# sinktheship.net
KiCad netlist of a schematic drawn in EAGLE
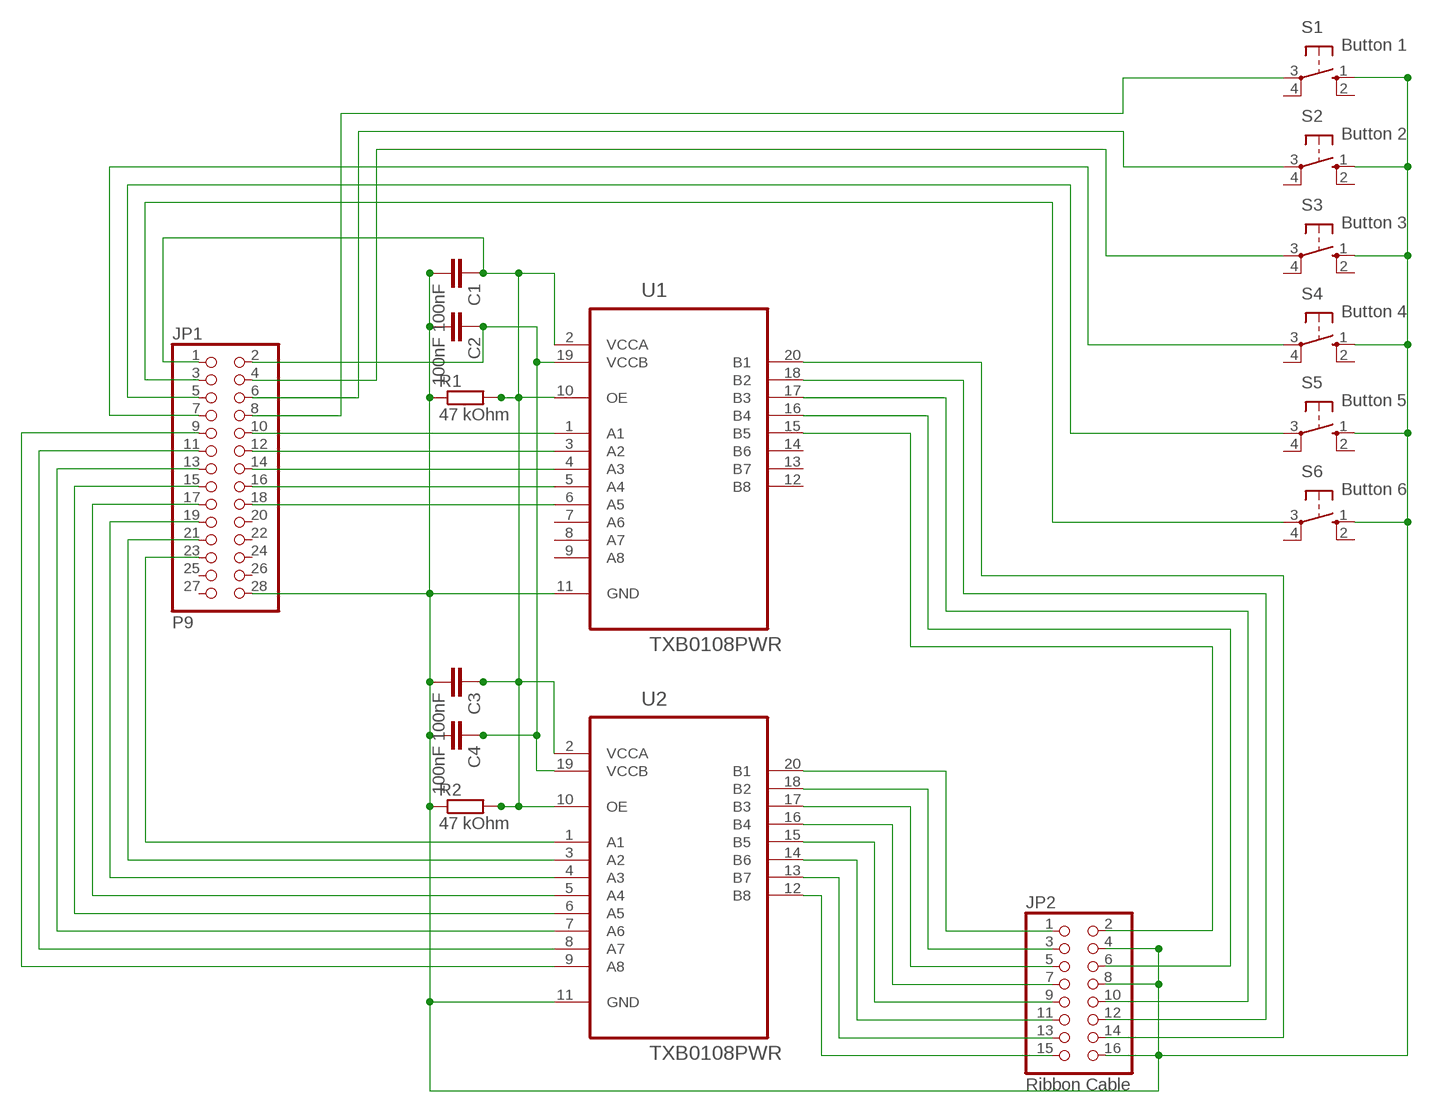
[diagram p0: schematic, sheet 1]

(export (version "E")
  (design (tool "Eeschema 10.0.6"))
  (components
    (comp (ref "C1")
      (value "100nF")
      (footprint "eagle-import:C0603")
      (libsource (lib "eagle-import") (part "C-EUC0603"))
    )
    (comp (ref "C2")
      (value "100nF")
      (footprint "eagle-import:C0603")
      (libsource (lib "eagle-import") (part "C-EUC0603"))
    )
    (comp (ref "C3")
      (value "100nF")
      (footprint "eagle-import:C0603")
      (libsource (lib "eagle-import") (part "C-EUC0603"))
    )
    (comp (ref "C4")
      (value "100nF")
      (footprint "eagle-import:C0603")
      (libsource (lib "eagle-import") (part "C-EUC0603"))
    )
    (comp (ref "JP1")
      (value "P9")
      (footprint "eagle-import:2X14")
      (libsource (lib "eagle-import") (part "PINHD-2X14"))
    )
    (comp (ref "JP2")
      (value "Ribbon Cable")
      (footprint "eagle-import:2X08")
      (libsource (lib "eagle-import") (part "PINHD-2X8"))
    )
    (comp (ref "R1")
      (value "47 kOhm")
      (footprint "eagle-import:R0603")
      (libsource (lib "eagle-import") (part "R-EU_R0603"))
    )
    (comp (ref "R2")
      (value "47 kOhm")
      (footprint "eagle-import:R0603")
      (libsource (lib "eagle-import") (part "R-EU_R0603"))
    )
    (comp (ref "S1")
      (value "Button 1")
      (footprint "eagle-import:B3F-10XX")
      (fields (field (name "MPN") "B3F-1000"))
      (libsource (lib "eagle-import") (part "10-XX"))
    )
    (comp (ref "S2")
      (value "Button 2")
      (footprint "eagle-import:B3F-10XX")
      (fields (field (name "MPN") "B3F-1000"))
      (libsource (lib "eagle-import") (part "10-XX"))
    )
    (comp (ref "S3")
      (value "Button 3")
      (footprint "eagle-import:B3F-10XX")
      (fields (field (name "MPN") "B3F-1000"))
      (libsource (lib "eagle-import") (part "10-XX"))
    )
    (comp (ref "S4")
      (value "Button 4")
      (footprint "eagle-import:B3F-10XX")
      (fields (field (name "MPN") "B3F-1000"))
      (libsource (lib "eagle-import") (part "10-XX"))
    )
    (comp (ref "S5")
      (value "Button 5")
      (footprint "eagle-import:B3F-10XX")
      (fields (field (name "MPN") "B3F-1000"))
      (libsource (lib "eagle-import") (part "10-XX"))
    )
    (comp (ref "S6")
      (value "Button 6")
      (footprint "eagle-import:B3F-10XX")
      (fields (field (name "MPN") "B3F-1000"))
      (libsource (lib "eagle-import") (part "10-XX"))
    )
    (comp (ref "U1")
      (value "TXB0108PWR")
      (footprint "eagle-import:SOP65P640X120-20N")
      (libsource (lib "eagle-import") (part "TXB0108PWR"))
    )
    (comp (ref "U2")
      (value "TXB0108PWR")
      (footprint "eagle-import:SOP65P640X120-20N")
      (libsource (lib "eagle-import") (part "TXB0108PWR"))
    )
  )
  (nets
    (net (code "1") (name "Net-(S1-P)") (class "Default")
      (node (ref "JP1") (pin "8") (pinfunction "8_8") (pintype "passive"))
      (node (ref "S1") (pin "3") (pinfunction "P_3") (pintype "passive"))
    )
    (net (code "2") (name "Net-(S1-S)") (class "Default")
      (node (ref "C1") (pin "2") (pinfunction "2_2") (pintype "passive"))
      (node (ref "C2") (pin "2") (pinfunction "2_2") (pintype "passive"))
      (node (ref "C3") (pin "2") (pinfunction "2_2") (pintype "passive"))
      (node (ref "C4") (pin "2") (pinfunction "2_2") (pintype "passive"))
      (node (ref "JP1") (pin "28") (pinfunction "28_28") (pintype "passive"))
      (node (ref "JP2") (pin "16") (pinfunction "16_16") (pintype "passive"))
      (node (ref "JP2") (pin "4") (pinfunction "4_4") (pintype "passive"))
      (node (ref "JP2") (pin "8") (pinfunction "8_8") (pintype "passive"))
      (node (ref "R1") (pin "1") (pinfunction "1_1") (pintype "passive"))
      (node (ref "R2") (pin "1") (pinfunction "1_1") (pintype "passive"))
      (node (ref "S1") (pin "1") (pinfunction "S_1") (pintype "passive"))
      (node (ref "S2") (pin "1") (pinfunction "S_1") (pintype "passive"))
      (node (ref "S3") (pin "1") (pinfunction "S_1") (pintype "passive"))
      (node (ref "S4") (pin "1") (pinfunction "S_1") (pintype "passive"))
      (node (ref "S5") (pin "1") (pinfunction "S_1") (pintype "passive"))
      (node (ref "S6") (pin "1") (pinfunction "S_1") (pintype "passive"))
      (node (ref "U1") (pin "11") (pinfunction "GND_11") (pintype "passive"))
      (node (ref "U2") (pin "11") (pinfunction "GND_11") (pintype "passive"))
    )
    (net (code "3") (name "Net-(S2-P)") (class "Default")
      (node (ref "JP1") (pin "6") (pinfunction "6_6") (pintype "passive"))
      (node (ref "S2") (pin "3") (pinfunction "P_3") (pintype "passive"))
    )
    (net (code "4") (name "Net-(S3-P)") (class "Default")
      (node (ref "JP1") (pin "4") (pinfunction "4_4") (pintype "passive"))
      (node (ref "S3") (pin "3") (pinfunction "P_3") (pintype "passive"))
    )
    (net (code "5") (name "Net-(S4-P)") (class "Default")
      (node (ref "JP1") (pin "7") (pinfunction "7_7") (pintype "passive"))
      (node (ref "S4") (pin "3") (pinfunction "P_3") (pintype "passive"))
    )
    (net (code "6") (name "Net-(S5-P)") (class "Default")
      (node (ref "JP1") (pin "5") (pinfunction "5_5") (pintype "passive"))
      (node (ref "S5") (pin "3") (pinfunction "P_3") (pintype "passive"))
    )
    (net (code "7") (name "Net-(S6-P)") (class "Default")
      (node (ref "JP1") (pin "3") (pinfunction "3_3") (pintype "passive"))
      (node (ref "S6") (pin "3") (pinfunction "P_3") (pintype "passive"))
    )
    (net (code "8") (name "Net-(U1-A1)") (class "Default")
      (node (ref "JP1") (pin "10") (pinfunction "10_10") (pintype "passive"))
      (node (ref "U1") (pin "1") (pinfunction "A1_1") (pintype "bidirectional"))
    )
    (net (code "9") (name "Net-(U1-A2)") (class "Default")
      (node (ref "JP1") (pin "12") (pinfunction "12_12") (pintype "passive"))
      (node (ref "U1") (pin "3") (pinfunction "A2_3") (pintype "bidirectional"))
    )
    (net (code "10") (name "Net-(U1-A3)") (class "Default")
      (node (ref "JP1") (pin "14") (pinfunction "14_14") (pintype "passive"))
      (node (ref "U1") (pin "4") (pinfunction "A3_4") (pintype "bidirectional"))
    )
    (net (code "11") (name "Net-(U1-A4)") (class "Default")
      (node (ref "JP1") (pin "16") (pinfunction "16_16") (pintype "passive"))
      (node (ref "U1") (pin "5") (pinfunction "A4_5") (pintype "bidirectional"))
    )
    (net (code "12") (name "Net-(U1-A5)") (class "Default")
      (node (ref "JP1") (pin "18") (pinfunction "18_18") (pintype "passive"))
      (node (ref "U1") (pin "6") (pinfunction "A5_6") (pintype "bidirectional"))
    )
    (net (code "13") (name "Net-(U1-B1)") (class "Default")
      (node (ref "JP2") (pin "14") (pinfunction "14_14") (pintype "passive"))
      (node (ref "U1") (pin "20") (pinfunction "B1_20") (pintype "bidirectional"))
    )
    (net (code "14") (name "Net-(U1-B2)") (class "Default")
      (node (ref "JP2") (pin "12") (pinfunction "12_12") (pintype "passive"))
      (node (ref "U1") (pin "18") (pinfunction "B2_18") (pintype "bidirectional"))
    )
    (net (code "15") (name "Net-(U1-B3)") (class "Default")
      (node (ref "JP2") (pin "10") (pinfunction "10_10") (pintype "passive"))
      (node (ref "U1") (pin "17") (pinfunction "B3_17") (pintype "bidirectional"))
    )
    (net (code "16") (name "Net-(U1-B4)") (class "Default")
      (node (ref "JP2") (pin "6") (pinfunction "6_6") (pintype "passive"))
      (node (ref "U1") (pin "16") (pinfunction "B4_16") (pintype "bidirectional"))
    )
    (net (code "17") (name "Net-(U1-B5)") (class "Default")
      (node (ref "JP2") (pin "2") (pinfunction "2_2") (pintype "passive"))
      (node (ref "U1") (pin "15") (pinfunction "B5_15") (pintype "bidirectional"))
    )
    (net (code "18") (name "Net-(U1-OE)") (class "Default")
      (node (ref "C1") (pin "1") (pinfunction "1_1") (pintype "passive"))
      (node (ref "C3") (pin "1") (pinfunction "1_1") (pintype "passive"))
      (node (ref "JP1") (pin "1") (pinfunction "1_1") (pintype "passive"))
      (node (ref "R1") (pin "2") (pinfunction "2_2") (pintype "passive"))
      (node (ref "R2") (pin "2") (pinfunction "2_2") (pintype "passive"))
      (node (ref "U1") (pin "10") (pinfunction "OE_10") (pintype "input"))
      (node (ref "U1") (pin "2") (pinfunction "VCCA_2") (pintype "power_in"))
      (node (ref "U2") (pin "10") (pinfunction "OE_10") (pintype "input"))
      (node (ref "U2") (pin "2") (pinfunction "VCCA_2") (pintype "power_in"))
    )
    (net (code "19") (name "Net-(U1-VCCB)") (class "Default")
      (node (ref "C2") (pin "1") (pinfunction "1_1") (pintype "passive"))
      (node (ref "C4") (pin "1") (pinfunction "1_1") (pintype "passive"))
      (node (ref "JP1") (pin "2") (pinfunction "2_2") (pintype "passive"))
      (node (ref "U1") (pin "19") (pinfunction "VCCB_19") (pintype "power_in"))
      (node (ref "U2") (pin "19") (pinfunction "VCCB_19") (pintype "power_in"))
    )
    (net (code "20") (name "Net-(U2-A1)") (class "Default")
      (node (ref "JP1") (pin "23") (pinfunction "23_23") (pintype "passive"))
      (node (ref "U2") (pin "1") (pinfunction "A1_1") (pintype "bidirectional"))
    )
    (net (code "21") (name "Net-(U2-A2)") (class "Default")
      (node (ref "JP1") (pin "21") (pinfunction "21_21") (pintype "passive"))
      (node (ref "U2") (pin "3") (pinfunction "A2_3") (pintype "bidirectional"))
    )
    (net (code "22") (name "Net-(U2-A3)") (class "Default")
      (node (ref "JP1") (pin "19") (pinfunction "19_19") (pintype "passive"))
      (node (ref "U2") (pin "4") (pinfunction "A3_4") (pintype "bidirectional"))
    )
    (net (code "23") (name "Net-(U2-A4)") (class "Default")
      (node (ref "JP1") (pin "17") (pinfunction "17_17") (pintype "passive"))
      (node (ref "U2") (pin "5") (pinfunction "A4_5") (pintype "bidirectional"))
    )
    (net (code "24") (name "Net-(U2-A5)") (class "Default")
      (node (ref "JP1") (pin "15") (pinfunction "15_15") (pintype "passive"))
      (node (ref "U2") (pin "6") (pinfunction "A5_6") (pintype "bidirectional"))
    )
    (net (code "25") (name "Net-(U2-A6)") (class "Default")
      (node (ref "JP1") (pin "13") (pinfunction "13_13") (pintype "passive"))
      (node (ref "U2") (pin "7") (pinfunction "A6_7") (pintype "bidirectional"))
    )
    (net (code "26") (name "Net-(U2-A7)") (class "Default")
      (node (ref "JP1") (pin "11") (pinfunction "11_11") (pintype "passive"))
      (node (ref "U2") (pin "8") (pinfunction "A7_8") (pintype "bidirectional"))
    )
    (net (code "27") (name "Net-(U2-A8)") (class "Default")
      (node (ref "JP1") (pin "9") (pinfunction "9_9") (pintype "passive"))
      (node (ref "U2") (pin "9") (pinfunction "A8_9") (pintype "bidirectional"))
    )
    (net (code "28") (name "Net-(U2-B1)") (class "Default")
      (node (ref "JP2") (pin "1") (pinfunction "1_1") (pintype "passive"))
      (node (ref "U2") (pin "20") (pinfunction "B1_20") (pintype "bidirectional"))
    )
    (net (code "29") (name "Net-(U2-B2)") (class "Default")
      (node (ref "JP2") (pin "3") (pinfunction "3_3") (pintype "passive"))
      (node (ref "U2") (pin "18") (pinfunction "B2_18") (pintype "bidirectional"))
    )
    (net (code "30") (name "Net-(U2-B3)") (class "Default")
      (node (ref "JP2") (pin "5") (pinfunction "5_5") (pintype "passive"))
      (node (ref "U2") (pin "17") (pinfunction "B3_17") (pintype "bidirectional"))
    )
    (net (code "31") (name "Net-(U2-B4)") (class "Default")
      (node (ref "JP2") (pin "7") (pinfunction "7_7") (pintype "passive"))
      (node (ref "U2") (pin "16") (pinfunction "B4_16") (pintype "bidirectional"))
    )
    (net (code "32") (name "Net-(U2-B5)") (class "Default")
      (node (ref "JP2") (pin "9") (pinfunction "9_9") (pintype "passive"))
      (node (ref "U2") (pin "15") (pinfunction "B5_15") (pintype "bidirectional"))
    )
    (net (code "33") (name "Net-(U2-B6)") (class "Default")
      (node (ref "JP2") (pin "11") (pinfunction "11_11") (pintype "passive"))
      (node (ref "U2") (pin "14") (pinfunction "B6_14") (pintype "bidirectional"))
    )
    (net (code "34") (name "Net-(U2-B7)") (class "Default")
      (node (ref "JP2") (pin "13") (pinfunction "13_13") (pintype "passive"))
      (node (ref "U2") (pin "13") (pinfunction "B7_13") (pintype "bidirectional"))
    )
    (net (code "35") (name "Net-(U2-B8)") (class "Default")
      (node (ref "JP2") (pin "15") (pinfunction "15_15") (pintype "passive"))
      (node (ref "U2") (pin "12") (pinfunction "B8_12") (pintype "bidirectional"))
    )
    (net (code "36") (name "unconnected-(JP1-Pad20)") (class "Default")
      (node (ref "JP1") (pin "20") (pinfunction "20_20") (pintype "passive"))
    )
    (net (code "37") (name "unconnected-(JP1-Pad22)") (class "Default")
      (node (ref "JP1") (pin "22") (pinfunction "22_22") (pintype "passive"))
    )
    (net (code "38") (name "unconnected-(JP1-Pad24)") (class "Default")
      (node (ref "JP1") (pin "24") (pinfunction "24_24") (pintype "passive"))
    )
    (net (code "39") (name "unconnected-(JP1-Pad25)") (class "Default")
      (node (ref "JP1") (pin "25") (pinfunction "25_25") (pintype "passive"))
    )
    (net (code "40") (name "unconnected-(JP1-Pad26)") (class "Default")
      (node (ref "JP1") (pin "26") (pinfunction "26_26") (pintype "passive"))
    )
    (net (code "41") (name "unconnected-(JP1-Pad27)") (class "Default")
      (node (ref "JP1") (pin "27") (pinfunction "27_27") (pintype "passive"))
    )
    (net (code "42") (name "unconnected-(S1-P1-Pad4)") (class "Default")
      (node (ref "S1") (pin "4") (pinfunction "P1_4") (pintype "passive"))
    )
    (net (code "43") (name "unconnected-(S1-S1-Pad2)") (class "Default")
      (node (ref "S1") (pin "2") (pinfunction "S1_2") (pintype "passive"))
    )
    (net (code "44") (name "unconnected-(S2-P1-Pad4)") (class "Default")
      (node (ref "S2") (pin "4") (pinfunction "P1_4") (pintype "passive"))
    )
    (net (code "45") (name "unconnected-(S2-S1-Pad2)") (class "Default")
      (node (ref "S2") (pin "2") (pinfunction "S1_2") (pintype "passive"))
    )
    (net (code "46") (name "unconnected-(S3-P1-Pad4)") (class "Default")
      (node (ref "S3") (pin "4") (pinfunction "P1_4") (pintype "passive"))
    )
    (net (code "47") (name "unconnected-(S3-S1-Pad2)") (class "Default")
      (node (ref "S3") (pin "2") (pinfunction "S1_2") (pintype "passive"))
    )
    (net (code "48") (name "unconnected-(S4-P1-Pad4)") (class "Default")
      (node (ref "S4") (pin "4") (pinfunction "P1_4") (pintype "passive"))
    )
    (net (code "49") (name "unconnected-(S4-S1-Pad2)") (class "Default")
      (node (ref "S4") (pin "2") (pinfunction "S1_2") (pintype "passive"))
    )
    (net (code "50") (name "unconnected-(S5-P1-Pad4)") (class "Default")
      (node (ref "S5") (pin "4") (pinfunction "P1_4") (pintype "passive"))
    )
    (net (code "51") (name "unconnected-(S5-S1-Pad2)") (class "Default")
      (node (ref "S5") (pin "2") (pinfunction "S1_2") (pintype "passive"))
    )
    (net (code "52") (name "unconnected-(S6-P1-Pad4)") (class "Default")
      (node (ref "S6") (pin "4") (pinfunction "P1_4") (pintype "passive"))
    )
    (net (code "53") (name "unconnected-(S6-S1-Pad2)") (class "Default")
      (node (ref "S6") (pin "2") (pinfunction "S1_2") (pintype "passive"))
    )
    (net (code "54") (name "unconnected-(U1-A6-Pad7)") (class "Default")
      (node (ref "U1") (pin "7") (pinfunction "A6_7") (pintype "bidirectional"))
    )
    (net (code "55") (name "unconnected-(U1-A7-Pad8)") (class "Default")
      (node (ref "U1") (pin "8") (pinfunction "A7_8") (pintype "bidirectional"))
    )
    (net (code "56") (name "unconnected-(U1-A8-Pad9)") (class "Default")
      (node (ref "U1") (pin "9") (pinfunction "A8_9") (pintype "bidirectional"))
    )
    (net (code "57") (name "unconnected-(U1-B6-Pad14)") (class "Default")
      (node (ref "U1") (pin "14") (pinfunction "B6_14") (pintype "bidirectional"))
    )
    (net (code "58") (name "unconnected-(U1-B7-Pad13)") (class "Default")
      (node (ref "U1") (pin "13") (pinfunction "B7_13") (pintype "bidirectional"))
    )
    (net (code "59") (name "unconnected-(U1-B8-Pad12)") (class "Default")
      (node (ref "U1") (pin "12") (pinfunction "B8_12") (pintype "bidirectional"))
    )
  )
)
